# MEZON_NEGATIVE.net
KiCad netlist of a schematic drawn in Altium Designer
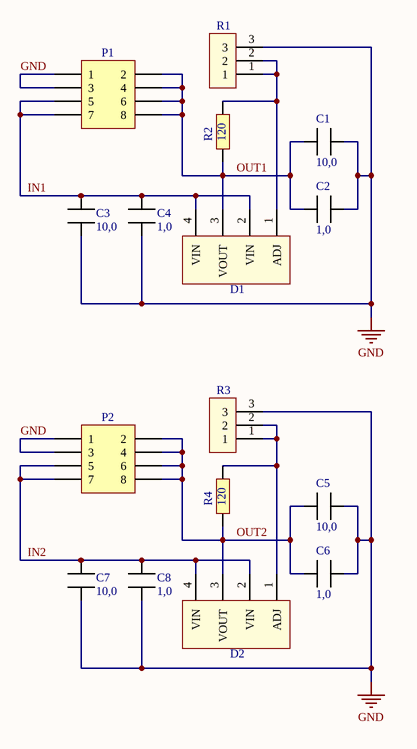
[diagram p0: MEZON_NEGATIVE.SchDoc]

(export (version "E")
  (design (tool "Eeschema 10.0.6"))
  (components
    (comp (ref "C1") (value "10,0") (footprint "Cap_BIG") (libsource (lib "Schlib") (part "CAP_BIG")))
    (comp (ref "C2") (value "1,0") (footprint "CAP_SMALL") (libsource (lib "Schlib") (part "CAP_SMALL")))
    (comp (ref "C3") (value "10,0") (footprint "Cap_BIG") (libsource (lib "Schlib") (part "CAP_BIG")))
    (comp (ref "C4") (value "1,0") (footprint "CAP_SMALL") (libsource (lib "Schlib") (part "CAP_SMALL")))
    (comp (ref "C5") (value "10,0") (footprint "Cap_BIG") (libsource (lib "Schlib") (part "CAP_BIG")))
    (comp (ref "C6") (value "1,0") (footprint "CAP_SMALL") (libsource (lib "Schlib") (part "CAP_SMALL")))
    (comp (ref "C7") (value "10,0") (footprint "Cap_BIG") (libsource (lib "Schlib") (part "CAP_BIG")))
    (comp (ref "C8") (value "1,0") (footprint "CAP_SMALL") (libsource (lib "Schlib") (part "CAP_SMALL")))
    (comp (ref "D1")
      (value "LM337")
      (footprint "SOT230P700X180-4N")
      (libsource (lib "Schlib") (part "LM337"))
    )
    (comp (ref "D2")
      (value "LM337")
      (footprint "SOT230P700X180-4N")
      (libsource (lib "Schlib") (part "LM337"))
    )
    (comp (ref "P1")
      (value "Header 4X2")
      (footprint "HDR2X4")
      (description "Header, 4-Pin, Dual row")
      (fields (field (name "PUBLISHER") "Altium Limited"))
      (libsource (lib "Miscellaneous Connectors") (part "Header 4X2"))
    )
    (comp (ref "P2")
      (value "Header 4X2")
      (footprint "HDR2X4")
      (description "Header, 4-Pin, Dual row")
      (fields (field (name "PUBLISHER") "Altium Limited"))
      (libsource (lib "Miscellaneous Connectors") (part "Header 4X2"))
    )
    (comp (ref "R1")
      (value "3296")
      (footprint "PODSTR_RES_3296")
      (libsource (lib "Schlib") (part "PODSTR_RES_NEW"))
    )
    (comp (ref "R2") (value "120") (footprint "RES") (libsource (lib "Schlib") (part "RES")))
    (comp (ref "R3")
      (value "3296")
      (footprint "PODSTR_RES_3296")
      (libsource (lib "Schlib") (part "PODSTR_RES_NEW"))
    )
    (comp (ref "R4") (value "120") (footprint "RES") (libsource (lib "Schlib") (part "RES")))
  )
  (nets
    (net (code "1") (name "/IN1") (class "Default")
      (node (ref "C3") (pin "2") (pinfunction "2_2") (pintype "passive"))
      (node (ref "C4") (pin "2") (pinfunction "2_2") (pintype "passive"))
      (node (ref "D1") (pin "2") (pinfunction "VIN_2") (pintype "passive"))
      (node (ref "D1") (pin "4") (pinfunction "VIN_4") (pintype "passive"))
      (node (ref "P1") (pin "5") (pinfunction "5_5") (pintype "passive"))
      (node (ref "P1") (pin "7") (pinfunction "7_7") (pintype "passive"))
    )
    (net (code "2") (name "/IN2") (class "Default")
      (node (ref "C7") (pin "2") (pinfunction "2_2") (pintype "passive"))
      (node (ref "C8") (pin "2") (pinfunction "2_2") (pintype "passive"))
      (node (ref "D2") (pin "2") (pinfunction "VIN_2") (pintype "passive"))
      (node (ref "D2") (pin "4") (pinfunction "VIN_4") (pintype "passive"))
      (node (ref "P2") (pin "5") (pinfunction "5_5") (pintype "passive"))
      (node (ref "P2") (pin "7") (pinfunction "7_7") (pintype "passive"))
    )
    (net (code "3") (name "/OUT1") (class "Default")
      (node (ref "C1") (pin "1") (pinfunction "1_1") (pintype "passive"))
      (node (ref "C2") (pin "2") (pinfunction "2_2") (pintype "passive"))
      (node (ref "D1") (pin "3") (pinfunction "VOUT_3") (pintype "passive"))
      (node (ref "P1") (pin "2") (pinfunction "2_2") (pintype "passive"))
      (node (ref "P1") (pin "4") (pinfunction "4_4") (pintype "passive"))
      (node (ref "P1") (pin "6") (pinfunction "6_6") (pintype "passive"))
      (node (ref "P1") (pin "8") (pinfunction "8_8") (pintype "passive"))
      (node (ref "R2") (pin "1") (pinfunction "1_1") (pintype "passive"))
    )
    (net (code "4") (name "/OUT2") (class "Default")
      (node (ref "C5") (pin "1") (pinfunction "1_1") (pintype "passive"))
      (node (ref "C6") (pin "2") (pinfunction "2_2") (pintype "passive"))
      (node (ref "D2") (pin "3") (pinfunction "VOUT_3") (pintype "passive"))
      (node (ref "P2") (pin "2") (pinfunction "2_2") (pintype "passive"))
      (node (ref "P2") (pin "4") (pinfunction "4_4") (pintype "passive"))
      (node (ref "P2") (pin "6") (pinfunction "6_6") (pintype "passive"))
      (node (ref "P2") (pin "8") (pinfunction "8_8") (pintype "passive"))
      (node (ref "R4") (pin "1") (pinfunction "1_1") (pintype "passive"))
    )
    (net (code "5") (name "GND") (class "Default")
      (node (ref "C1") (pin "2") (pinfunction "2_2") (pintype "passive"))
      (node (ref "C2") (pin "1") (pinfunction "1_1") (pintype "passive"))
      (node (ref "C3") (pin "1") (pinfunction "1_1") (pintype "passive"))
      (node (ref "C4") (pin "1") (pinfunction "1_1") (pintype "passive"))
      (node (ref "C5") (pin "2") (pinfunction "2_2") (pintype "passive"))
      (node (ref "C6") (pin "1") (pinfunction "1_1") (pintype "passive"))
      (node (ref "C7") (pin "1") (pinfunction "1_1") (pintype "passive"))
      (node (ref "C8") (pin "1") (pinfunction "1_1") (pintype "passive"))
      (node (ref "P1") (pin "1") (pinfunction "1_1") (pintype "passive"))
      (node (ref "P1") (pin "3") (pinfunction "3_3") (pintype "passive"))
      (node (ref "P2") (pin "1") (pinfunction "1_1") (pintype "passive"))
      (node (ref "P2") (pin "3") (pinfunction "3_3") (pintype "passive"))
      (node (ref "R1") (pin "3") (pinfunction "3_3") (pintype "passive"))
      (node (ref "R3") (pin "3") (pinfunction "3_3") (pintype "passive"))
    )
    (net (code "6") (name "Net-(D1-ADJ)") (class "Default")
      (node (ref "D1") (pin "1") (pinfunction "ADJ_1") (pintype "passive"))
      (node (ref "R1") (pin "1") (pinfunction "1_1") (pintype "passive"))
      (node (ref "R1") (pin "2") (pinfunction "2_2") (pintype "passive"))
      (node (ref "R2") (pin "2") (pinfunction "2_2") (pintype "passive"))
    )
    (net (code "7") (name "Net-(D2-ADJ)") (class "Default")
      (node (ref "D2") (pin "1") (pinfunction "ADJ_1") (pintype "passive"))
      (node (ref "R3") (pin "1") (pinfunction "1_1") (pintype "passive"))
      (node (ref "R3") (pin "2") (pinfunction "2_2") (pintype "passive"))
      (node (ref "R4") (pin "2") (pinfunction "2_2") (pintype "passive"))
    )
  )
)
